# Adapter.net
KiCad netlist of a schematic drawn in Altium Designer
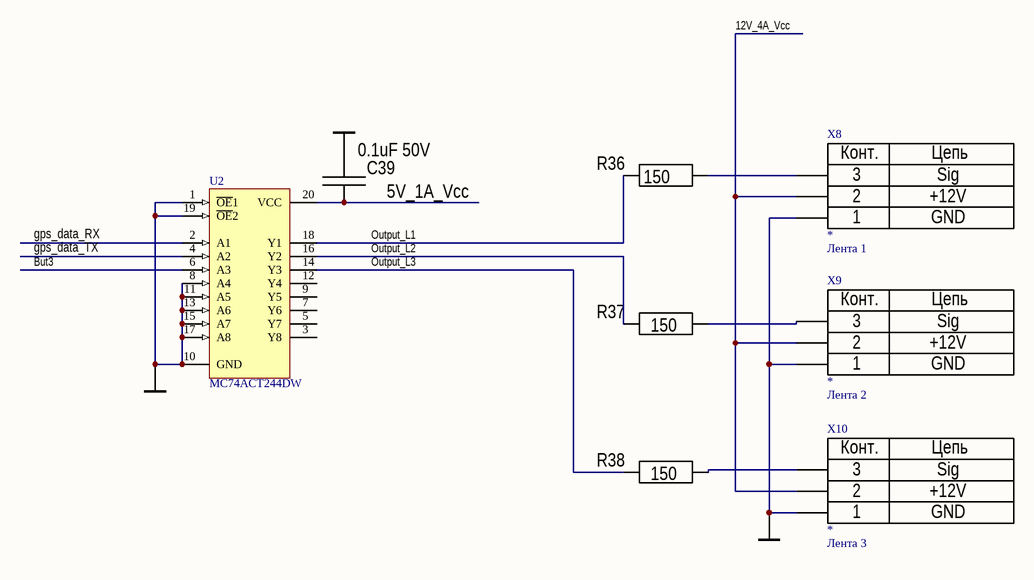
[diagram p0: Adapter.SchDoc]

(export (version "E")
  (design (tool "Eeschema 10.0.6"))
  (components
    (comp (ref "C39")
      (value "0.1uF 50V")
      (footprint "0805_CAP")
      (libsource (lib "Integrated_Library_tikhovikt") (part "Cap_np"))
    )
    (comp (ref "R36")
      (value "150")
      (footprint "0805_RES")
      (libsource (lib "Integrated_Library_tikhovikt") (part "Res"))
    )
    (comp (ref "R37")
      (value "150")
      (footprint "0805_RES")
      (libsource (lib "Integrated_Library_tikhovikt") (part "Res"))
    )
    (comp (ref "R38")
      (value "150")
      (footprint "0805_RES")
      (libsource (lib "Integrated_Library_tikhovikt") (part "Res"))
    )
    (comp (ref "U2")
      (value "MC74ACT244DW")
      (footprint "751D-04_N")
      (description "Octal Buffer/Line Driver with 3-State Outputs")
      (fields (field (name "PUBLISHER") "Altium Limited"))
      (libsource (lib "ON Semi Logic Buffer Line Driver") (part "MC74ACT244DW"))
    )
    (comp (ref "X8")
      (value "*")
      (footprint "3pad_5.08")
      (fields (field (name "DESTINY") "Лента 1"))
      (libsource (lib "Integrated_Library_tikhovikt") (part "3pin_conn"))
    )
    (comp (ref "X9")
      (value "*")
      (footprint "3pad_5.08")
      (fields (field (name "DESTINY") "Лента 2"))
      (libsource (lib "Integrated_Library_tikhovikt") (part "3pin_conn"))
    )
    (comp (ref "X10")
      (value "*")
      (footprint "3pad_5.08")
      (fields (field (name "DESTINY") "Лента 3"))
      (libsource (lib "Integrated_Library_tikhovikt") (part "3pin_conn"))
    )
  )
  (nets
    (net (code "2") (name "/12V_4A_Vcc") (class "Default")
      (node (ref "X10") (pin "2") (pinfunction "2_2") (pintype "passive"))
      (node (ref "X8") (pin "2") (pinfunction "2_2") (pintype "passive"))
      (node (ref "X9") (pin "2") (pinfunction "2_2") (pintype "passive"))
    )
    (net (code "3") (name "/But3") (class "Default")
      (node (ref "U2") (pin "6") (pinfunction "A3_6") (pintype "input"))
    )
    (net (code "4") (name "/Output_L1") (class "Default")
      (node (ref "R36") (pin "1") (pinfunction "1_1") (pintype "passive"))
      (node (ref "U2") (pin "18") (pinfunction "Y1_18") (pintype "tri_state"))
    )
    (net (code "5") (name "/Output_L2") (class "Default")
      (node (ref "R37") (pin "1") (pinfunction "1_1") (pintype "passive"))
      (node (ref "U2") (pin "16") (pinfunction "Y2_16") (pintype "tri_state"))
    )
    (net (code "6") (name "/Output_L3") (class "Default")
      (node (ref "R38") (pin "1") (pinfunction "1_1") (pintype "passive"))
      (node (ref "U2") (pin "14") (pinfunction "Y3_14") (pintype "tri_state"))
    )
    (net (code "7") (name "/gps_data_RX") (class "Default")
      (node (ref "U2") (pin "2") (pinfunction "A1_2") (pintype "input"))
    )
    (net (code "8") (name "/gps_data_TX") (class "Default")
      (node (ref "U2") (pin "4") (pinfunction "A2_4") (pintype "input"))
    )
    (net (code "9") (name "GND") (class "Default")
      (node (ref "C39") (pin "2") (pinfunction "2_2") (pintype "passive"))
      (node (ref "U2") (pin "1") (pinfunction "~{OE}1_1") (pintype "input"))
      (node (ref "U2") (pin "10") (pinfunction "GND_10") (pintype "power_in"))
      (node (ref "U2") (pin "11") (pinfunction "A5_11") (pintype "input"))
      (node (ref "U2") (pin "13") (pinfunction "A6_13") (pintype "input"))
      (node (ref "U2") (pin "15") (pinfunction "A7_15") (pintype "input"))
      (node (ref "U2") (pin "17") (pinfunction "A8_17") (pintype "input"))
      (node (ref "U2") (pin "19") (pinfunction "~{OE}2_19") (pintype "input"))
      (node (ref "U2") (pin "8") (pinfunction "A4_8") (pintype "input"))
      (node (ref "X10") (pin "1") (pinfunction "1_1") (pintype "passive"))
      (node (ref "X8") (pin "1") (pinfunction "1_1") (pintype "passive"))
      (node (ref "X9") (pin "1") (pinfunction "1_1") (pintype "passive"))
    )
    (net (code "10") (name "Net-(R36-Pad2)") (class "Default")
      (node (ref "R36") (pin "2") (pinfunction "2_2") (pintype "passive"))
      (node (ref "X8") (pin "3") (pinfunction "3_3") (pintype "passive"))
    )
    (net (code "11") (name "Net-(R37-Pad2)") (class "Default")
      (node (ref "R37") (pin "2") (pinfunction "2_2") (pintype "passive"))
      (node (ref "X9") (pin "3") (pinfunction "3_3") (pintype "passive"))
    )
    (net (code "12") (name "Net-(R38-Pad2)") (class "Default")
      (node (ref "R38") (pin "2") (pinfunction "2_2") (pintype "passive"))
      (node (ref "X10") (pin "3") (pinfunction "3_3") (pintype "passive"))
    )
    (net (code "13") (name "Net-(U2-VCC)") (class "Default")
      (node (ref "C39") (pin "1") (pinfunction "1_1") (pintype "passive"))
      (node (ref "U2") (pin "20") (pinfunction "VCC_20") (pintype "power_in"))
    )
    (net (code "14") (name "unconnected-(U2-Y4-Pad12)") (class "Default")
      (node (ref "U2") (pin "12") (pinfunction "Y4_12") (pintype "tri_state"))
    )
    (net (code "15") (name "unconnected-(U2-Y5-Pad9)") (class "Default")
      (node (ref "U2") (pin "9") (pinfunction "Y5_9") (pintype "tri_state"))
    )
    (net (code "16") (name "unconnected-(U2-Y6-Pad7)") (class "Default")
      (node (ref "U2") (pin "7") (pinfunction "Y6_7") (pintype "tri_state"))
    )
    (net (code "17") (name "unconnected-(U2-Y7-Pad5)") (class "Default")
      (node (ref "U2") (pin "5") (pinfunction "Y7_5") (pintype "tri_state"))
    )
    (net (code "18") (name "unconnected-(U2-Y8-Pad3)") (class "Default")
      (node (ref "U2") (pin "3") (pinfunction "Y8_3") (pintype "tri_state"))
    )
  )
)
